# HEBoard_ver4.net
KiCad netlist of a schematic drawn in Altium Designer
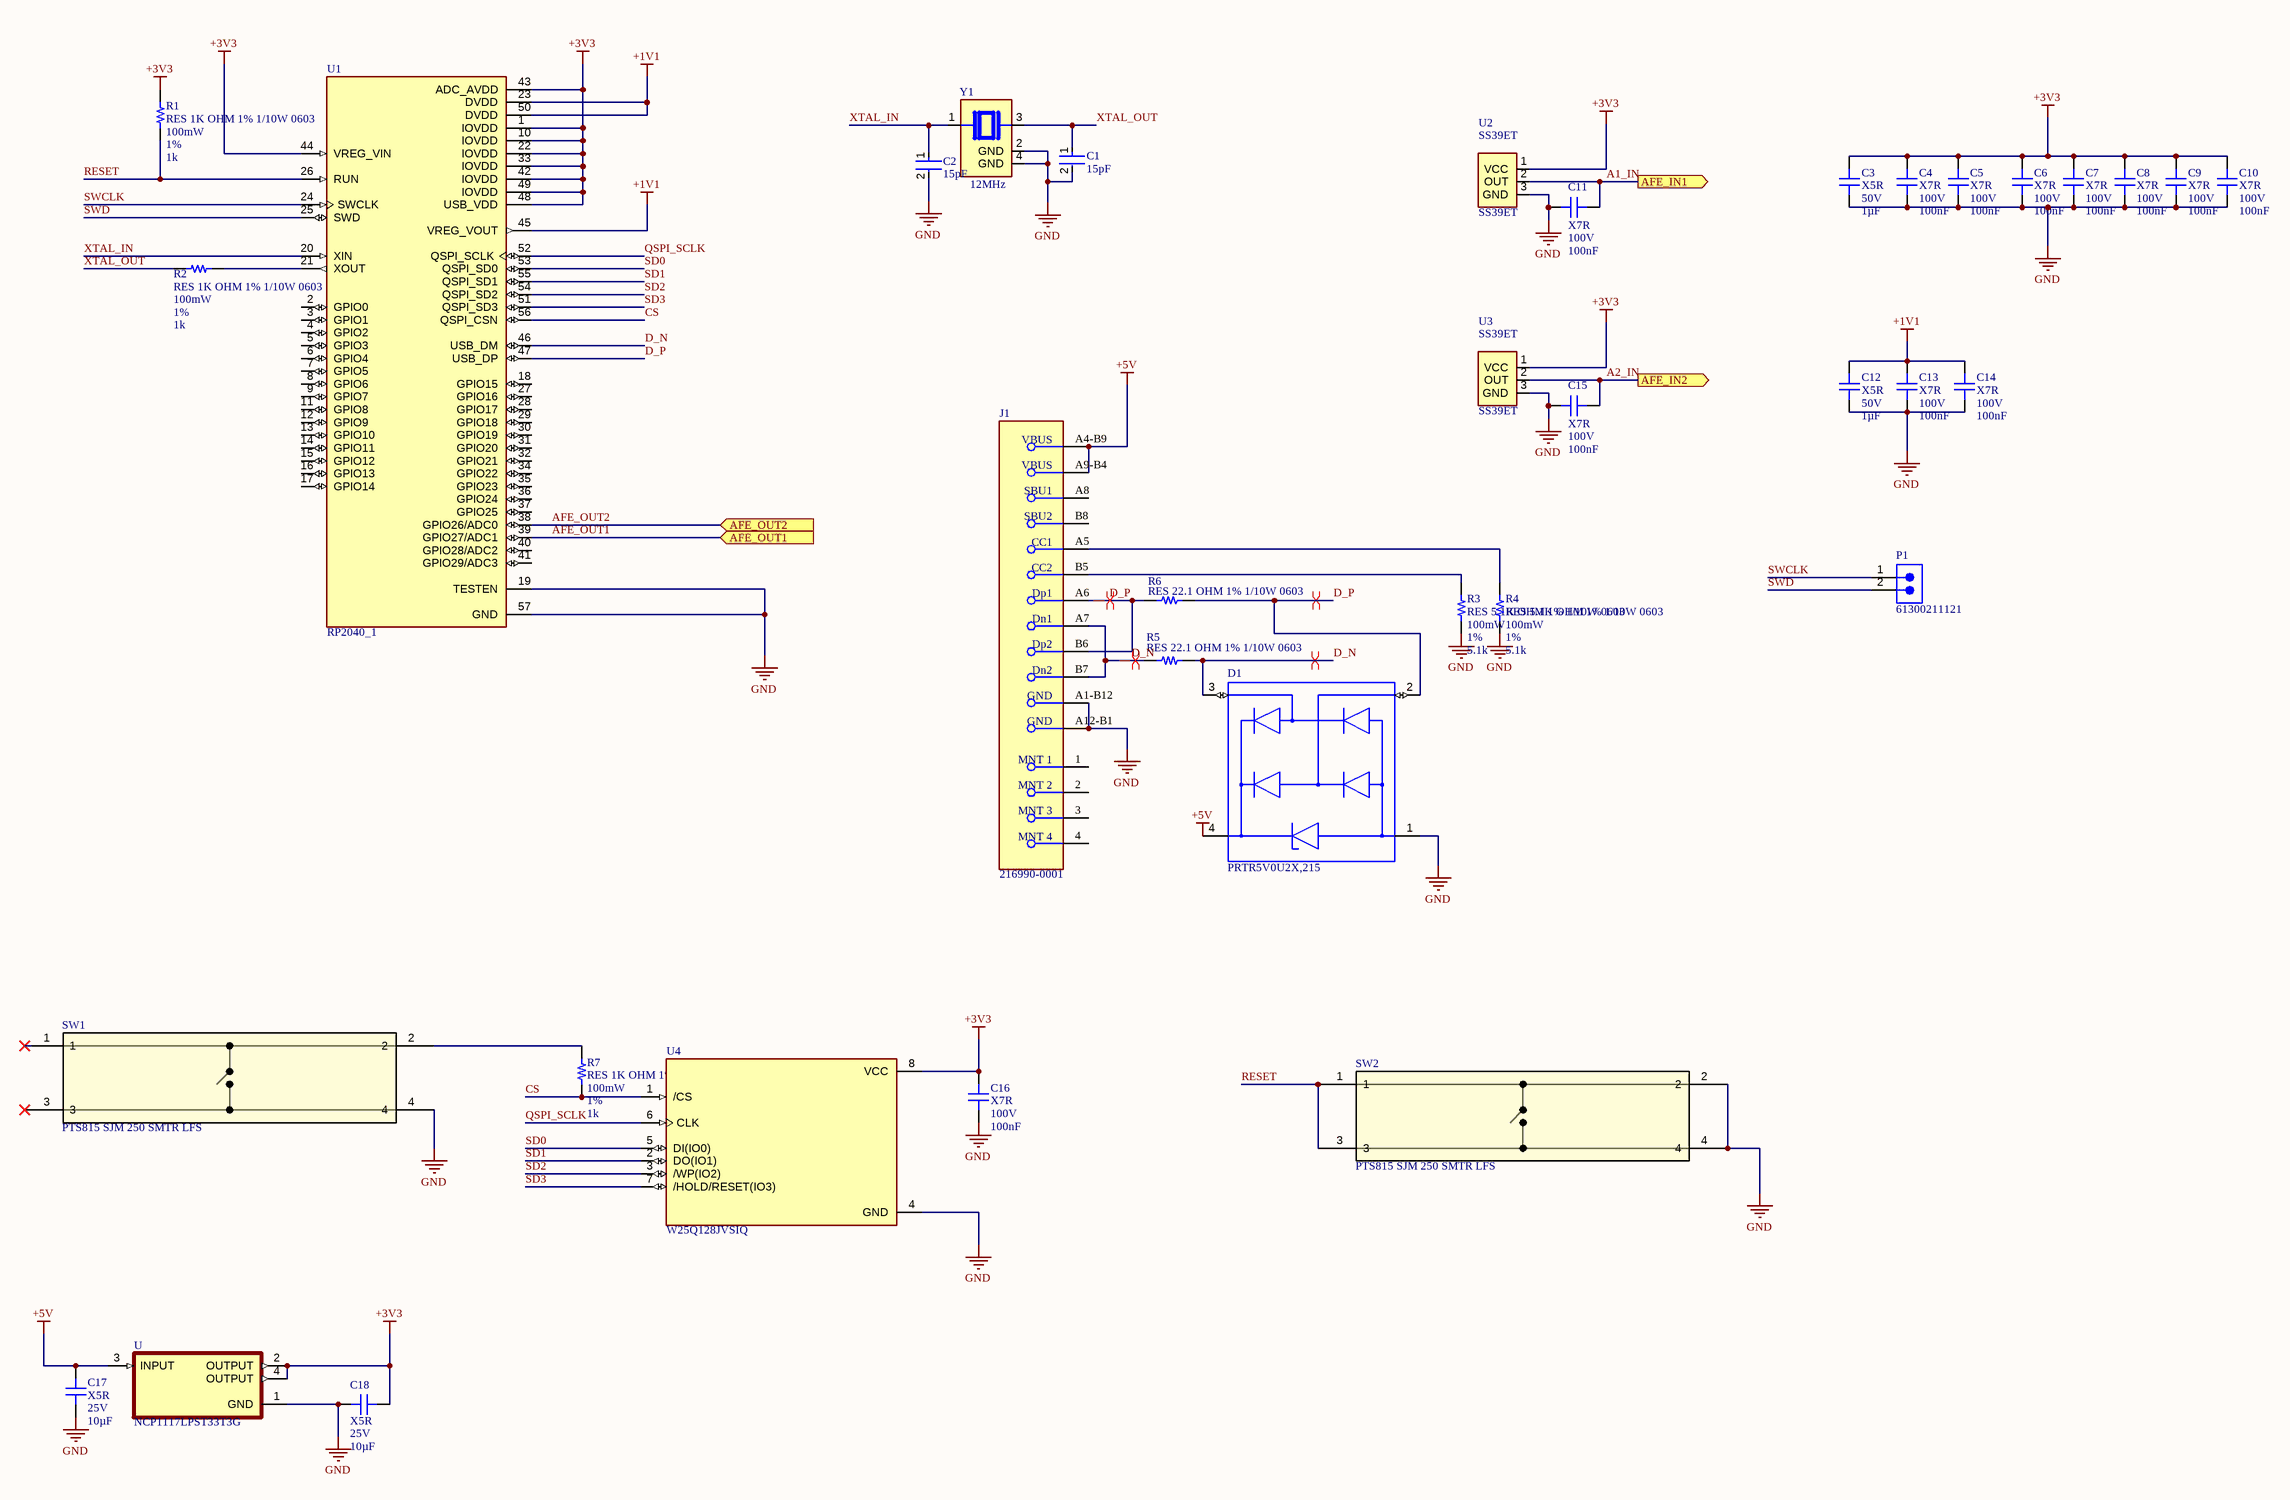
[diagram p0: HEBoard_ver4.SchDoc]

(export (version "E")
  (design (tool "Eeschema 10.0.6"))
  (components
    (comp (ref "C1")
      (value "15pF")
      (footprint "FP-CC0603-0_9-MFG")
      (description "CAP CER 15PF 50V C0G/NPO 0603")
      (fields (field (name "TOLERANCE") "5%"))
      (libsource (lib "Altium Content Vault") (part "11868f565c42a9108669ba33697ecf6"))
    )
    (comp (ref "C2")
      (value "15pF")
      (footprint "FP-CC0603-0_9-MFG")
      (description "CAP CER 15PF 50V C0G/NPO 0603")
      (fields (field (name "TOLERANCE") "5%"))
      (libsource (lib "Altium Content Vault") (part "11868f565c42a9108669ba33697ecf6"))
    )
    (comp (ref "C3")
      (value "CAP CER 1UF 50V X5R 0603")
      (footprint "CAP 0603_1608")
      (description "1µF ±10% 50V Ceramic Capacitor X7R 0603 (1608 Metric)")
      (fields
        (field (name "DIELECTRIC CODE") "X5R")
        (field (name "VOLTAGE RATING") "50V")
        (field (name "CAPACITANCE") "1µF")
        (field (name "TOLERANCE") "10%")
      )
      (libsource (lib "Midnight Sun") (part "Capacitor"))
    )
    (comp (ref "C4")
      (value "CAP CER 0.1UF 100V 10% X7R 0603")
      (footprint "CAP 0603_1608")
      (fields
        (field (name "DIELECTRIC CODE") "X7R")
        (field (name "VOLTAGE RATING") "100V")
        (field (name "CAPACITANCE") "100nF")
        (field (name "TOLERANCE") "10%")
      )
      (libsource (lib "Midnight Sun") (part "Capacitor"))
    )
    (comp (ref "C5")
      (value "CAP CER 0.1UF 100V 10% X7R 0603")
      (footprint "CAP 0603_1608")
      (fields
        (field (name "DIELECTRIC CODE") "X7R")
        (field (name "VOLTAGE RATING") "100V")
        (field (name "CAPACITANCE") "100nF")
        (field (name "TOLERANCE") "10%")
      )
      (libsource (lib "Midnight Sun") (part "Capacitor"))
    )
    (comp (ref "C6")
      (value "CAP CER 0.1UF 100V 10% X7R 0603")
      (footprint "CAP 0603_1608")
      (fields
        (field (name "DIELECTRIC CODE") "X7R")
        (field (name "VOLTAGE RATING") "100V")
        (field (name "CAPACITANCE") "100nF")
        (field (name "TOLERANCE") "10%")
      )
      (libsource (lib "Midnight Sun") (part "Capacitor"))
    )
    (comp (ref "C7")
      (value "CAP CER 0.1UF 100V 10% X7R 0603")
      (footprint "CAP 0603_1608")
      (fields
        (field (name "DIELECTRIC CODE") "X7R")
        (field (name "VOLTAGE RATING") "100V")
        (field (name "CAPACITANCE") "100nF")
        (field (name "TOLERANCE") "10%")
      )
      (libsource (lib "Midnight Sun") (part "Capacitor"))
    )
    (comp (ref "C8")
      (value "CAP CER 0.1UF 100V 10% X7R 0603")
      (footprint "CAP 0603_1608")
      (fields
        (field (name "DIELECTRIC CODE") "X7R")
        (field (name "VOLTAGE RATING") "100V")
        (field (name "CAPACITANCE") "100nF")
        (field (name "TOLERANCE") "10%")
      )
      (libsource (lib "Midnight Sun") (part "Capacitor"))
    )
    (comp (ref "C9")
      (value "CAP CER 0.1UF 100V 10% X7R 0603")
      (footprint "CAP 0603_1608")
      (fields
        (field (name "DIELECTRIC CODE") "X7R")
        (field (name "VOLTAGE RATING") "100V")
        (field (name "CAPACITANCE") "100nF")
        (field (name "TOLERANCE") "10%")
      )
      (libsource (lib "Midnight Sun") (part "Capacitor"))
    )
    (comp (ref "C10")
      (value "CAP CER 0.1UF 100V 10% X7R 0603")
      (footprint "CAP 0603_1608")
      (fields
        (field (name "DIELECTRIC CODE") "X7R")
        (field (name "VOLTAGE RATING") "100V")
        (field (name "CAPACITANCE") "100nF")
        (field (name "TOLERANCE") "10%")
      )
      (libsource (lib "Midnight Sun") (part "Capacitor"))
    )
    (comp (ref "C11")
      (value "CAP CER 0.1UF 100V 10% X7R 0603")
      (footprint "CAP 0603_1608")
      (fields
        (field (name "DIELECTRIC CODE") "X7R")
        (field (name "VOLTAGE RATING") "100V")
        (field (name "CAPACITANCE") "100nF")
        (field (name "TOLERANCE") "10%")
      )
      (libsource (lib "Midnight Sun") (part "Capacitor"))
    )
    (comp (ref "C12")
      (value "CAP CER 1UF 50V X5R 0603")
      (footprint "CAP 0603_1608")
      (description "1µF ±10% 50V Ceramic Capacitor X7R 0603 (1608 Metric)")
      (fields
        (field (name "DIELECTRIC CODE") "X5R")
        (field (name "VOLTAGE RATING") "50V")
        (field (name "CAPACITANCE") "1µF")
        (field (name "TOLERANCE") "10%")
      )
      (libsource (lib "Midnight Sun") (part "Capacitor"))
    )
    (comp (ref "C13")
      (value "CAP CER 0.1UF 100V 10% X7R 0603")
      (footprint "CAP 0603_1608")
      (fields
        (field (name "DIELECTRIC CODE") "X7R")
        (field (name "VOLTAGE RATING") "100V")
        (field (name "CAPACITANCE") "100nF")
        (field (name "TOLERANCE") "10%")
      )
      (libsource (lib "Midnight Sun") (part "Capacitor"))
    )
    (comp (ref "C14")
      (value "CAP CER 0.1UF 100V 10% X7R 0603")
      (footprint "CAP 0603_1608")
      (fields
        (field (name "DIELECTRIC CODE") "X7R")
        (field (name "VOLTAGE RATING") "100V")
        (field (name "CAPACITANCE") "100nF")
        (field (name "TOLERANCE") "10%")
      )
      (libsource (lib "Midnight Sun") (part "Capacitor"))
    )
    (comp (ref "C15")
      (value "CAP CER 0.1UF 100V 10% X7R 0603")
      (footprint "CAP 0603_1608")
      (fields
        (field (name "DIELECTRIC CODE") "X7R")
        (field (name "VOLTAGE RATING") "100V")
        (field (name "CAPACITANCE") "100nF")
        (field (name "TOLERANCE") "10%")
      )
      (libsource (lib "Midnight Sun") (part "Capacitor"))
    )
    (comp (ref "C16")
      (value "CAP CER 0.1UF 100V 10% X7R 0603")
      (footprint "CAP 0603_1608")
      (fields
        (field (name "DIELECTRIC CODE") "X7R")
        (field (name "VOLTAGE RATING") "100V")
        (field (name "CAPACITANCE") "100nF")
        (field (name "TOLERANCE") "10%")
      )
      (libsource (lib "Midnight Sun") (part "Capacitor"))
    )
    (comp (ref "C17")
      (value "CAP CER 10UF 25V 20% X5R 0603")
      (footprint "CAP 0603_1608")
      (description "10µF ±20% 25V Ceramic Capacitor X5R 0603 (1608 Metric)")
      (fields
        (field (name "DIELECTRIC CODE") "X5R")
        (field (name "VOLTAGE RATING") "25V")
        (field (name "CAPACITANCE") "10µF")
        (field (name "TOLERANCE") "20%")
      )
      (libsource (lib "Midnight Sun") (part "Capacitor"))
    )
    (comp (ref "C18")
      (value "CAP CER 10UF 25V 20% X5R 0603")
      (footprint "CAP 0603_1608")
      (description "10µF ±20% 25V Ceramic Capacitor X5R 0603 (1608 Metric)")
      (fields
        (field (name "DIELECTRIC CODE") "X5R")
        (field (name "VOLTAGE RATING") "25V")
        (field (name "CAPACITANCE") "10µF")
        (field (name "TOLERANCE") "20%")
      )
      (libsource (lib "Midnight Sun") (part "Capacitor"))
    )
    (comp (ref "D1")
      (value "PRTR5V0U2X,215")
      (footprint "FP-SOT143B-MFG")
      (description "TVS DIODE 5.5V SOT143B")
      (libsource (lib "Altium Content Vault") (part "31e4fa1655694efd507c8a671e666ef"))
    )
    (comp (ref "J1")
      (value "216990-0001")
      (footprint "FP-216990-0001-MFG")
      (description "CONN RCP USB2.0 TYP C 24P SMD RA")
      (libsource (lib "Altium Content Vault") (part "6e83beadf304854e588eb0595046805"))
    )
    (comp (ref "P1")
      (value "61300211121")
      (footprint "61300211121")
      (libsource (lib "Altium Content Vault") (part "Header_Male_1R_02P"))
    )
    (comp (ref "R1")
      (value "RES 1K OHM 1% 1/10W 0603")
      (footprint "RES 0603_1608")
      (description "1 kOhms ±1% 0.1W, 1/10W Chip Resistor 0603 (1608 Metric) Moisture Resistant Thick Film")
      (fields
        (field (name "POWER RATING") "100mW")
        (field (name "TOLERANCE") "1%")
        (field (name "RESISTANCE") "1k")
      )
      (libsource (lib "Midnight Sun") (part "Resistor"))
    )
    (comp (ref "R2")
      (value "RES 1K OHM 1% 1/10W 0603")
      (footprint "RES 0603_1608")
      (description "1 kOhms ±1% 0.1W, 1/10W Chip Resistor 0603 (1608 Metric) Moisture Resistant Thick Film")
      (fields
        (field (name "POWER RATING") "100mW")
        (field (name "TOLERANCE") "1%")
        (field (name "RESISTANCE") "1k")
      )
      (libsource (lib "Midnight Sun") (part "Resistor"))
    )
    (comp (ref "R3")
      (value "RES 5.1K OHM 1% 1/10W 0603")
      (footprint "RES 0603_1608")
      (description "5.1 kOhms ±1% 0.1W, 1/10W Chip Resistor 0603 (1608 Metric) Automotive AEC-Q200 Thick Film")
      (fields
        (field (name "POWER RATING") "100mW")
        (field (name "TOLERANCE") "1%")
        (field (name "RESISTANCE") "5.1k")
      )
      (libsource (lib "Midnight Sun") (part "Resistor"))
    )
    (comp (ref "R4")
      (value "RES 5.1K OHM 1% 1/10W 0603")
      (footprint "RES 0603_1608")
      (description "5.1 kOhms ±1% 0.1W, 1/10W Chip Resistor 0603 (1608 Metric) Automotive AEC-Q200 Thick Film")
      (fields
        (field (name "POWER RATING") "100mW")
        (field (name "TOLERANCE") "1%")
        (field (name "RESISTANCE") "5.1k")
      )
      (libsource (lib "Midnight Sun") (part "Resistor"))
    )
    (comp (ref "R5")
      (value "RES 22.1 OHM 1% 1/10W 0603")
      (footprint "RES 0603_1608")
      (libsource (lib "Midnight Sun") (part "Resistor"))
    )
    (comp (ref "R6")
      (value "RES 22.1 OHM 1% 1/10W 0603")
      (footprint "RES 0603_1608")
      (libsource (lib "Midnight Sun") (part "Resistor"))
    )
    (comp (ref "R7")
      (value "RES 1K OHM 1% 1/10W 0603")
      (footprint "RES 0603_1608")
      (description "1 kOhms ±1% 0.1W, 1/10W Chip Resistor 0603 (1608 Metric) Moisture Resistant Thick Film")
      (fields
        (field (name "POWER RATING") "100mW")
        (field (name "TOLERANCE") "1%")
        (field (name "RESISTANCE") "1k")
      )
      (libsource (lib "Midnight Sun") (part "Resistor"))
    )
    (comp (ref "SW1")
      (value "PTS815 SJM 250 SMTR LFS")
      (footprint "SW4_PTS815 SJM 250 SMTR LFS_CNK")
      (description "No Description Available")
      (libsource (lib "HEBoard_ver4") (part "PTS815 SJM 250 SMTR LFS"))
    )
    (comp (ref "SW2")
      (value "PTS815 SJM 250 SMTR LFS")
      (footprint "SW4_PTS815 SJM 250 SMTR LFS_CNK")
      (description "No Description Available")
      (libsource (lib "HEBoard_ver4") (part "PTS815 SJM 250 SMTR LFS"))
    )
    (comp (ref "U")
      (value "NCP1117LPST33T3G")
      (footprint "HEBoard_ver4:SOT230P700X175-4N")
      (description "Linear Voltage Regulator IC 1 Output 1A SOT-223")
      (fields (field (name "MF") "ON Semiconductor"))
      (libsource (lib "HEBoard_ver4") (part "NCP1117LPST33T3G"))
    )
    (comp (ref "U1")
      (value "RP2040_1")
      (footprint "QFN40P700X700X90-57N")
      (description "RP2040 chip for Raspberry Pi Pico - ARMÂ® CortexÂ®-M0+ MCU 32-Bit")
      (fields (field (name "MP") "RP2040") (field (name "MF") "Raspberry Pi"))
      (libsource (lib "HEBoard_ver4") (part "RP2040_1"))
    )
    (comp (ref "U2")
      (value "SS39ET")
      (footprint "CHRY-MX1A-11NW_V")
      (description "analog Hall Effect Sensor 1.5 mA 2.7 - 6.5 V dc ¦ Honeywell SS39ET")
      (fields (field (name "MF") "Honeywell Sensing and Productivity Solutions"))
      (libsource (lib "HEBoard_ver4") (part "SS39ET"))
    )
    (comp (ref "U3")
      (value "SS39ET")
      (footprint "CHRY-MX1A-11NW_V")
      (description "analog Hall Effect Sensor 1.5 mA 2.7 - 6.5 V dc ¦ Honeywell SS39ET")
      (fields (field (name "MF") "Honeywell Sensing and Productivity Solutions"))
      (libsource (lib "HEBoard_ver4") (part "SS39ET"))
    )
    (comp (ref "U4")
      (value "W25Q128JVSIQ")
      (footprint "HEBoard_ver4:SOIC127P790X216-8N")
      (description "FLASH - NOR Memory IC 128Mb (16M x 8) SPI - Quad I/O, QPI, DTR 133 MHz 8-SOIC")
      (fields (field (name "MF") "Winbond Electronics"))
      (libsource (lib "HEBoard_ver4") (part "W25Q128JVSIQ"))
    )
    (comp (ref "Y1")
      (value "12MHz")
      (footprint "XTAL_ABM8G-12.000MHZ-4Y-T3")
      (description "12 MHz Â±30ppm Crystal 10pF 120 Ohms 4-SMD, No Lead")
      (fields (field (name "MF") "Abracon") (field (name "MP") "ABM8G-12.000MHZ-4Y-T3"))
      (libsource (lib "HEBoard_ver4") (part "ABM8G-12.000MHZ-4Y-T3"))
    )
  )
  (nets
    (net (code "1") (name "+1V1") (class "Default")
      (node (ref "C12") (pin "2") (pinfunction "2_2") (pintype "passive"))
      (node (ref "C13") (pin "2") (pinfunction "2_2") (pintype "passive"))
      (node (ref "C14") (pin "2") (pinfunction "2_2") (pintype "passive"))
      (node (ref "U1") (pin "23") (pinfunction "DVDD_23") (pintype "power_in"))
      (node (ref "U1") (pin "45") (pinfunction "VREG_VOUT_45") (pintype "output"))
      (node (ref "U1") (pin "50") (pinfunction "DVDD_50") (pintype "power_in"))
    )
    (net (code "2") (name "+3V3") (class "Default")
      (node (ref "C10") (pin "2") (pinfunction "2_2") (pintype "passive"))
      (node (ref "C16") (pin "2") (pinfunction "2_2") (pintype "passive"))
      (node (ref "C18") (pin "1") (pinfunction "1_1") (pintype "passive"))
      (node (ref "C3") (pin "2") (pinfunction "2_2") (pintype "passive"))
      (node (ref "C4") (pin "2") (pinfunction "2_2") (pintype "passive"))
      (node (ref "C5") (pin "2") (pinfunction "2_2") (pintype "passive"))
      (node (ref "C6") (pin "2") (pinfunction "2_2") (pintype "passive"))
      (node (ref "C7") (pin "2") (pinfunction "2_2") (pintype "passive"))
      (node (ref "C8") (pin "2") (pinfunction "2_2") (pintype "passive"))
      (node (ref "C9") (pin "2") (pinfunction "2_2") (pintype "passive"))
      (node (ref "R1") (pin "2") (pinfunction "2_2") (pintype "passive"))
      (node (ref "U") (pin "2") (pinfunction "OUTPUT_2") (pintype "output"))
      (node (ref "U") (pin "4") (pinfunction "OUTPUT_4") (pintype "output"))
      (node (ref "U1") (pin "1") (pinfunction "IOVDD_1") (pintype "power_in"))
      (node (ref "U1") (pin "10") (pinfunction "IOVDD_10") (pintype "power_in"))
      (node (ref "U1") (pin "22") (pinfunction "IOVDD_22") (pintype "power_in"))
      (node (ref "U1") (pin "33") (pinfunction "IOVDD_33") (pintype "power_in"))
      (node (ref "U1") (pin "42") (pinfunction "IOVDD_42") (pintype "power_in"))
      (node (ref "U1") (pin "43") (pinfunction "ADC_AVDD_43") (pintype "power_in"))
      (node (ref "U1") (pin "44") (pinfunction "VREG_VIN_44") (pintype "input"))
      (node (ref "U1") (pin "48") (pinfunction "USB_VDD_48") (pintype "power_in"))
      (node (ref "U1") (pin "49") (pinfunction "IOVDD_49") (pintype "power_in"))
      (node (ref "U2") (pin "1") (pinfunction "VCC_1") (pintype "passive"))
      (node (ref "U3") (pin "1") (pinfunction "VCC_1") (pintype "passive"))
      (node (ref "U4") (pin "8") (pinfunction "VCC_8") (pintype "power_in"))
    )
    (net (code "3") (name "+5V") (class "Default")
      (node (ref "C17") (pin "2") (pinfunction "2_2") (pintype "passive"))
      (node (ref "D1") (pin "4") (pinfunction "VCC_4") (pintype "power_in"))
      (node (ref "J1") (pin "A4-B9") (pinfunction "VBUS_A4-B9") (pintype "passive"))
      (node (ref "J1") (pin "A9-B4") (pinfunction "VBUS_A9-B4") (pintype "passive"))
      (node (ref "U") (pin "3") (pinfunction "INPUT_3") (pintype "input"))
    )
    (net (code "4") (name "/A1_IN") (class "Default")
      (node (ref "C11") (pin "1") (pinfunction "1_1") (pintype "passive"))
      (node (ref "U2") (pin "2") (pinfunction "OUT_2") (pintype "passive"))
    )
    (net (code "5") (name "/A2_IN") (class "Default")
      (node (ref "C15") (pin "1") (pinfunction "1_1") (pintype "passive"))
      (node (ref "U3") (pin "2") (pinfunction "OUT_2") (pintype "passive"))
    )
    (net (code "6") (name "/AFE_OUT1") (class "Default")
      (node (ref "U1") (pin "39") (pinfunction "GPIO27/ADC1_39") (pintype "bidirectional"))
    )
    (net (code "7") (name "/AFE_OUT2") (class "Default")
      (node (ref "U1") (pin "38") (pinfunction "GPIO26/ADC0_38") (pintype "bidirectional"))
    )
    (net (code "8") (name "/CS") (class "Default")
      (node (ref "R7") (pin "2") (pinfunction "2_2") (pintype "passive"))
      (node (ref "U1") (pin "56") (pinfunction "QSPI_CSN_56") (pintype "bidirectional"))
      (node (ref "U4") (pin "1") (pinfunction "/CS_1") (pintype "input"))
    )
    (net (code "9") (name "/D_N") (class "Default")
      (node (ref "D1") (pin "3") (pinfunction "I/O_2_3") (pintype "bidirectional"))
      (node (ref "J1") (pin "A7") (pinfunction "Dn1_A7") (pintype "passive"))
      (node (ref "J1") (pin "B7") (pinfunction "Dn2_B7") (pintype "passive"))
      (node (ref "R5") (pin "1") (pinfunction "1_1") (pintype "passive"))
      (node (ref "R5") (pin "2") (pinfunction "2_2") (pintype "passive"))
      (node (ref "U1") (pin "46") (pinfunction "USB_DM_46") (pintype "bidirectional"))
    )
    (net (code "10") (name "/D_P") (class "Default")
      (node (ref "D1") (pin "2") (pinfunction "I/O_1_2") (pintype "bidirectional"))
      (node (ref "J1") (pin "A6") (pinfunction "Dp1_A6") (pintype "passive"))
      (node (ref "J1") (pin "B6") (pinfunction "Dp2_B6") (pintype "passive"))
      (node (ref "R6") (pin "1") (pinfunction "1_1") (pintype "passive"))
      (node (ref "R6") (pin "2") (pinfunction "2_2") (pintype "passive"))
      (node (ref "U1") (pin "47") (pinfunction "USB_DP_47") (pintype "bidirectional"))
    )
    (net (code "11") (name "/QSPI_SCLK") (class "Default")
      (node (ref "U1") (pin "52") (pinfunction "QSPI_SCLK_52") (pintype "bidirectional"))
      (node (ref "U4") (pin "6") (pinfunction "CLK_6") (pintype "input"))
    )
    (net (code "12") (name "/RESET") (class "Default")
      (node (ref "R1") (pin "1") (pinfunction "1_1") (pintype "passive"))
      (node (ref "SW2") (pin "1") (pinfunction "1_1") (pintype "passive"))
      (node (ref "SW2") (pin "3") (pinfunction "3_3") (pintype "passive"))
      (node (ref "U1") (pin "26") (pinfunction "RUN_26") (pintype "input"))
    )
    (net (code "13") (name "/SD0") (class "Default")
      (node (ref "U1") (pin "53") (pinfunction "QSPI_SD0_53") (pintype "bidirectional"))
      (node (ref "U4") (pin "5") (pinfunction "DI(IO0)_5") (pintype "bidirectional"))
    )
    (net (code "14") (name "/SD1") (class "Default")
      (node (ref "U1") (pin "55") (pinfunction "QSPI_SD1_55") (pintype "bidirectional"))
      (node (ref "U4") (pin "2") (pinfunction "DO(IO1)_2") (pintype "bidirectional"))
    )
    (net (code "15") (name "/SD2") (class "Default")
      (node (ref "U1") (pin "54") (pinfunction "QSPI_SD2_54") (pintype "bidirectional"))
      (node (ref "U4") (pin "3") (pinfunction "/WP(IO2)_3") (pintype "bidirectional"))
    )
    (net (code "16") (name "/SD3") (class "Default")
      (node (ref "U1") (pin "51") (pinfunction "QSPI_SD3_51") (pintype "bidirectional"))
      (node (ref "U4") (pin "7") (pinfunction "/HOLD/RESET(IO3)_7") (pintype "bidirectional"))
    )
    (net (code "17") (name "/SWCLK") (class "Default")
      (node (ref "P1") (pin "1") (pinfunction "1_1") (pintype "passive"))
      (node (ref "U1") (pin "24") (pinfunction "SWCLK_24") (pintype "input"))
    )
    (net (code "18") (name "/SWD") (class "Default")
      (node (ref "P1") (pin "2") (pinfunction "2_2") (pintype "passive"))
      (node (ref "U1") (pin "25") (pinfunction "SWD_25") (pintype "bidirectional"))
    )
    (net (code "19") (name "/XTAL_IN") (class "Default")
      (node (ref "C2") (pin "1") (pinfunction "1_1") (pintype "passive"))
      (node (ref "U1") (pin "20") (pinfunction "XIN_20") (pintype "input"))
      (node (ref "Y1") (pin "1") (pinfunction "1_1") (pintype "passive"))
    )
    (net (code "20") (name "/XTAL_OUT") (class "Default")
      (node (ref "C1") (pin "1") (pinfunction "1_1") (pintype "passive"))
      (node (ref "R2") (pin "2") (pinfunction "2_2") (pintype "passive"))
      (node (ref "Y1") (pin "3") (pinfunction "2_3") (pintype "passive"))
    )
    (net (code "21") (name "GND") (class "Default")
      (node (ref "C1") (pin "2") (pinfunction "2_2") (pintype "passive"))
      (node (ref "C10") (pin "1") (pinfunction "1_1") (pintype "passive"))
      (node (ref "C11") (pin "2") (pinfunction "2_2") (pintype "passive"))
      (node (ref "C12") (pin "1") (pinfunction "1_1") (pintype "passive"))
      (node (ref "C13") (pin "1") (pinfunction "1_1") (pintype "passive"))
      (node (ref "C14") (pin "1") (pinfunction "1_1") (pintype "passive"))
      (node (ref "C15") (pin "2") (pinfunction "2_2") (pintype "passive"))
      (node (ref "C16") (pin "1") (pinfunction "1_1") (pintype "passive"))
      (node (ref "C17") (pin "1") (pinfunction "1_1") (pintype "passive"))
      (node (ref "C18") (pin "2") (pinfunction "2_2") (pintype "passive"))
      (node (ref "C2") (pin "2") (pinfunction "2_2") (pintype "passive"))
      (node (ref "C3") (pin "1") (pinfunction "1_1") (pintype "passive"))
      (node (ref "C4") (pin "1") (pinfunction "1_1") (pintype "passive"))
      (node (ref "C5") (pin "1") (pinfunction "1_1") (pintype "passive"))
      (node (ref "C6") (pin "1") (pinfunction "1_1") (pintype "passive"))
      (node (ref "C7") (pin "1") (pinfunction "1_1") (pintype "passive"))
      (node (ref "C8") (pin "1") (pinfunction "1_1") (pintype "passive"))
      (node (ref "C9") (pin "1") (pinfunction "1_1") (pintype "passive"))
      (node (ref "D1") (pin "1") (pinfunction "GND_1") (pintype "power_in"))
      (node (ref "J1") (pin "A1-B12") (pinfunction "GND_A1-B12") (pintype "passive"))
      (node (ref "J1") (pin "A12-B1") (pinfunction "GND_A12-B1") (pintype "passive"))
      (node (ref "R3") (pin "1") (pinfunction "1_1") (pintype "passive"))
      (node (ref "R4") (pin "1") (pinfunction "1_1") (pintype "passive"))
      (node (ref "SW1") (pin "4") (pinfunction "4_4") (pintype "passive"))
      (node (ref "SW2") (pin "2") (pinfunction "2_2") (pintype "passive"))
      (node (ref "SW2") (pin "4") (pinfunction "4_4") (pintype "passive"))
      (node (ref "U") (pin "1") (pinfunction "GND_1") (pintype "power_in"))
      (node (ref "U1") (pin "19") (pinfunction "TESTEN_19") (pintype "passive"))
      (node (ref "U1") (pin "57") (pinfunction "GND_57") (pintype "power_in"))
      (node (ref "U2") (pin "3") (pinfunction "GND_3") (pintype "passive"))
      (node (ref "U3") (pin "3") (pinfunction "GND_3") (pintype "passive"))
      (node (ref "U4") (pin "4") (pinfunction "GND_4") (pintype "power_in"))
      (node (ref "Y1") (pin "2") (pinfunction "GND_2") (pintype "power_in"))
      (node (ref "Y1") (pin "4") (pinfunction "GND_4") (pintype "power_in"))
    )
    (net (code "22") (name "Net-(J1-CC1)") (class "Default")
      (node (ref "J1") (pin "A5") (pinfunction "CC1_A5") (pintype "passive"))
      (node (ref "R4") (pin "2") (pinfunction "2_2") (pintype "passive"))
    )
    (net (code "23") (name "Net-(J1-CC2)") (class "Default")
      (node (ref "J1") (pin "B5") (pinfunction "CC2_B5") (pintype "passive"))
      (node (ref "R3") (pin "2") (pinfunction "2_2") (pintype "passive"))
    )
    (net (code "24") (name "Net-(R7-Pad1)") (class "Default")
      (node (ref "R7") (pin "1") (pinfunction "1_1") (pintype "passive"))
      (node (ref "SW1") (pin "2") (pinfunction "2_2") (pintype "passive"))
    )
    (net (code "25") (name "Net-(U1-XOUT)") (class "Default")
      (node (ref "R2") (pin "1") (pinfunction "1_1") (pintype "passive"))
      (node (ref "U1") (pin "21") (pinfunction "XOUT_21") (pintype "output"))
    )
    (net (code "26") (name "unconnected-(J1-MNT_1-Pad1)") (class "Default")
      (node (ref "J1") (pin "1") (pinfunction "MNT_1_1") (pintype "passive"))
    )
    (net (code "27") (name "unconnected-(J1-MNT_2-Pad2)") (class "Default")
      (node (ref "J1") (pin "2") (pinfunction "MNT_2_2") (pintype "passive"))
    )
    (net (code "28") (name "unconnected-(J1-MNT_3-Pad3)") (class "Default")
      (node (ref "J1") (pin "3") (pinfunction "MNT_3_3") (pintype "passive"))
    )
    (net (code "29") (name "unconnected-(J1-MNT_4-Pad4)") (class "Default")
      (node (ref "J1") (pin "4") (pinfunction "MNT_4_4") (pintype "passive"))
    )
    (net (code "30") (name "unconnected-(J1-SBU1-PadA8)") (class "Default")
      (node (ref "J1") (pin "A8") (pinfunction "SBU1_A8") (pintype "passive"))
    )
    (net (code "31") (name "unconnected-(J1-SBU2-PadB8)") (class "Default")
      (node (ref "J1") (pin "B8") (pinfunction "SBU2_B8") (pintype "passive"))
    )
    (net (code "32") (name "unconnected-(SW1-Pad1)") (class "Default")
      (node (ref "SW1") (pin "1") (pinfunction "1_1") (pintype "passive+no_connect"))
    )
    (net (code "33") (name "unconnected-(SW1-Pad3)") (class "Default")
      (node (ref "SW1") (pin "3") (pinfunction "3_3") (pintype "passive+no_connect"))
    )
    (net (code "34") (name "unconnected-(U1-GPIO0-Pad2)") (class "Default")
      (node (ref "U1") (pin "2") (pinfunction "GPIO0_2") (pintype "bidirectional"))
    )
    (net (code "35") (name "unconnected-(U1-GPIO1-Pad3)") (class "Default")
      (node (ref "U1") (pin "3") (pinfunction "GPIO1_3") (pintype "bidirectional"))
    )
    (net (code "36") (name "unconnected-(U1-GPIO2-Pad4)") (class "Default")
      (node (ref "U1") (pin "4") (pinfunction "GPIO2_4") (pintype "bidirectional"))
    )
    (net (code "37") (name "unconnected-(U1-GPIO3-Pad5)") (class "Default")
      (node (ref "U1") (pin "5") (pinfunction "GPIO3_5") (pintype "bidirectional"))
    )
    (net (code "38") (name "unconnected-(U1-GPIO4-Pad6)") (class "Default")
      (node (ref "U1") (pin "6") (pinfunction "GPIO4_6") (pintype "bidirectional"))
    )
    (net (code "39") (name "unconnected-(U1-GPIO5-Pad7)") (class "Default")
      (node (ref "U1") (pin "7") (pinfunction "GPIO5_7") (pintype "bidirectional"))
    )
    (net (code "40") (name "unconnected-(U1-GPIO6-Pad8)") (class "Default")
      (node (ref "U1") (pin "8") (pinfunction "GPIO6_8") (pintype "bidirectional"))
    )
    (net (code "41") (name "unconnected-(U1-GPIO7-Pad9)") (class "Default")
      (node (ref "U1") (pin "9") (pinfunction "GPIO7_9") (pintype "bidirectional"))
    )
    (net (code "42") (name "unconnected-(U1-GPIO8-Pad11)") (class "Default")
      (node (ref "U1") (pin "11") (pinfunction "GPIO8_11") (pintype "bidirectional"))
    )
    (net (code "43") (name "unconnected-(U1-GPIO9-Pad12)") (class "Default")
      (node (ref "U1") (pin "12") (pinfunction "GPIO9_12") (pintype "bidirectional"))
    )
    (net (code "44") (name "unconnected-(U1-GPIO10-Pad13)") (class "Default")
      (node (ref "U1") (pin "13") (pinfunction "GPIO10_13") (pintype "bidirectional"))
    )
    (net (code "45") (name "unconnected-(U1-GPIO11-Pad14)") (class "Default")
      (node (ref "U1") (pin "14") (pinfunction "GPIO11_14") (pintype "bidirectional"))
    )
    (net (code "46") (name "unconnected-(U1-GPIO12-Pad15)") (class "Default")
      (node (ref "U1") (pin "15") (pinfunction "GPIO12_15") (pintype "bidirectional"))
    )
    (net (code "47") (name "unconnected-(U1-GPIO13-Pad16)") (class "Default")
      (node (ref "U1") (pin "16") (pinfunction "GPIO13_16") (pintype "bidirectional"))
    )
    (net (code "48") (name "unconnected-(U1-GPIO14-Pad17)") (class "Default")
      (node (ref "U1") (pin "17") (pinfunction "GPIO14_17") (pintype "bidirectional"))
    )
    (net (code "49") (name "unconnected-(U1-GPIO15-Pad18)") (class "Default")
      (node (ref "U1") (pin "18") (pinfunction "GPIO15_18") (pintype "bidirectional"))
    )
    (net (code "50") (name "unconnected-(U1-GPIO16-Pad27)") (class "Default")
      (node (ref "U1") (pin "27") (pinfunction "GPIO16_27") (pintype "bidirectional"))
    )
    (net (code "51") (name "unconnected-(U1-GPIO17-Pad28)") (class "Default")
      (node (ref "U1") (pin "28") (pinfunction "GPIO17_28") (pintype "bidirectional"))
    )
    (net (code "52") (name "unconnected-(U1-GPIO18-Pad29)") (class "Default")
      (node (ref "U1") (pin "29") (pinfunction "GPIO18_29") (pintype "bidirectional"))
    )
    (net (code "53") (name "unconnected-(U1-GPIO19-Pad30)") (class "Default")
      (node (ref "U1") (pin "30") (pinfunction "GPIO19_30") (pintype "bidirectional"))
    )
    (net (code "54") (name "unconnected-(U1-GPIO20-Pad31)") (class "Default")
      (node (ref "U1") (pin "31") (pinfunction "GPIO20_31") (pintype "bidirectional"))
    )
    (net (code "55") (name "unconnected-(U1-GPIO21-Pad32)") (class "Default")
      (node (ref "U1") (pin "32") (pinfunction "GPIO21_32") (pintype "bidirectional"))
    )
    (net (code "56") (name "unconnected-(U1-GPIO22-Pad34)") (class "Default")
      (node (ref "U1") (pin "34") (pinfunction "GPIO22_34") (pintype "bidirectional"))
    )
    (net (code "57") (name "unconnected-(U1-GPIO23-Pad35)") (class "Default")
      (node (ref "U1") (pin "35") (pinfunction "GPIO23_35") (pintype "bidirectional"))
    )
    (net (code "58") (name "unconnected-(U1-GPIO24-Pad36)") (class "Default")
      (node (ref "U1") (pin "36") (pinfunction "GPIO24_36") (pintype "bidirectional"))
    )
    (net (code "59") (name "unconnected-(U1-GPIO25-Pad37)") (class "Default")
      (node (ref "U1") (pin "37") (pinfunction "GPIO25_37") (pintype "bidirectional"))
    )
    (net (code "60") (name "unconnected-(U1-GPIO28{slash}ADC2-Pad40)") (class "Default")
      (node (ref "U1") (pin "40") (pinfunction "GPIO28/ADC2_40") (pintype "bidirectional"))
    )
    (net (code "61") (name "unconnected-(U1-GPIO29{slash}ADC3-Pad41)") (class "Default")
      (node (ref "U1") (pin "41") (pinfunction "GPIO29/ADC3_41") (pintype "bidirectional"))
    )
  )
)
